# MCU063A_USB.net
KiCad netlist of a schematic drawn in Altium Designer
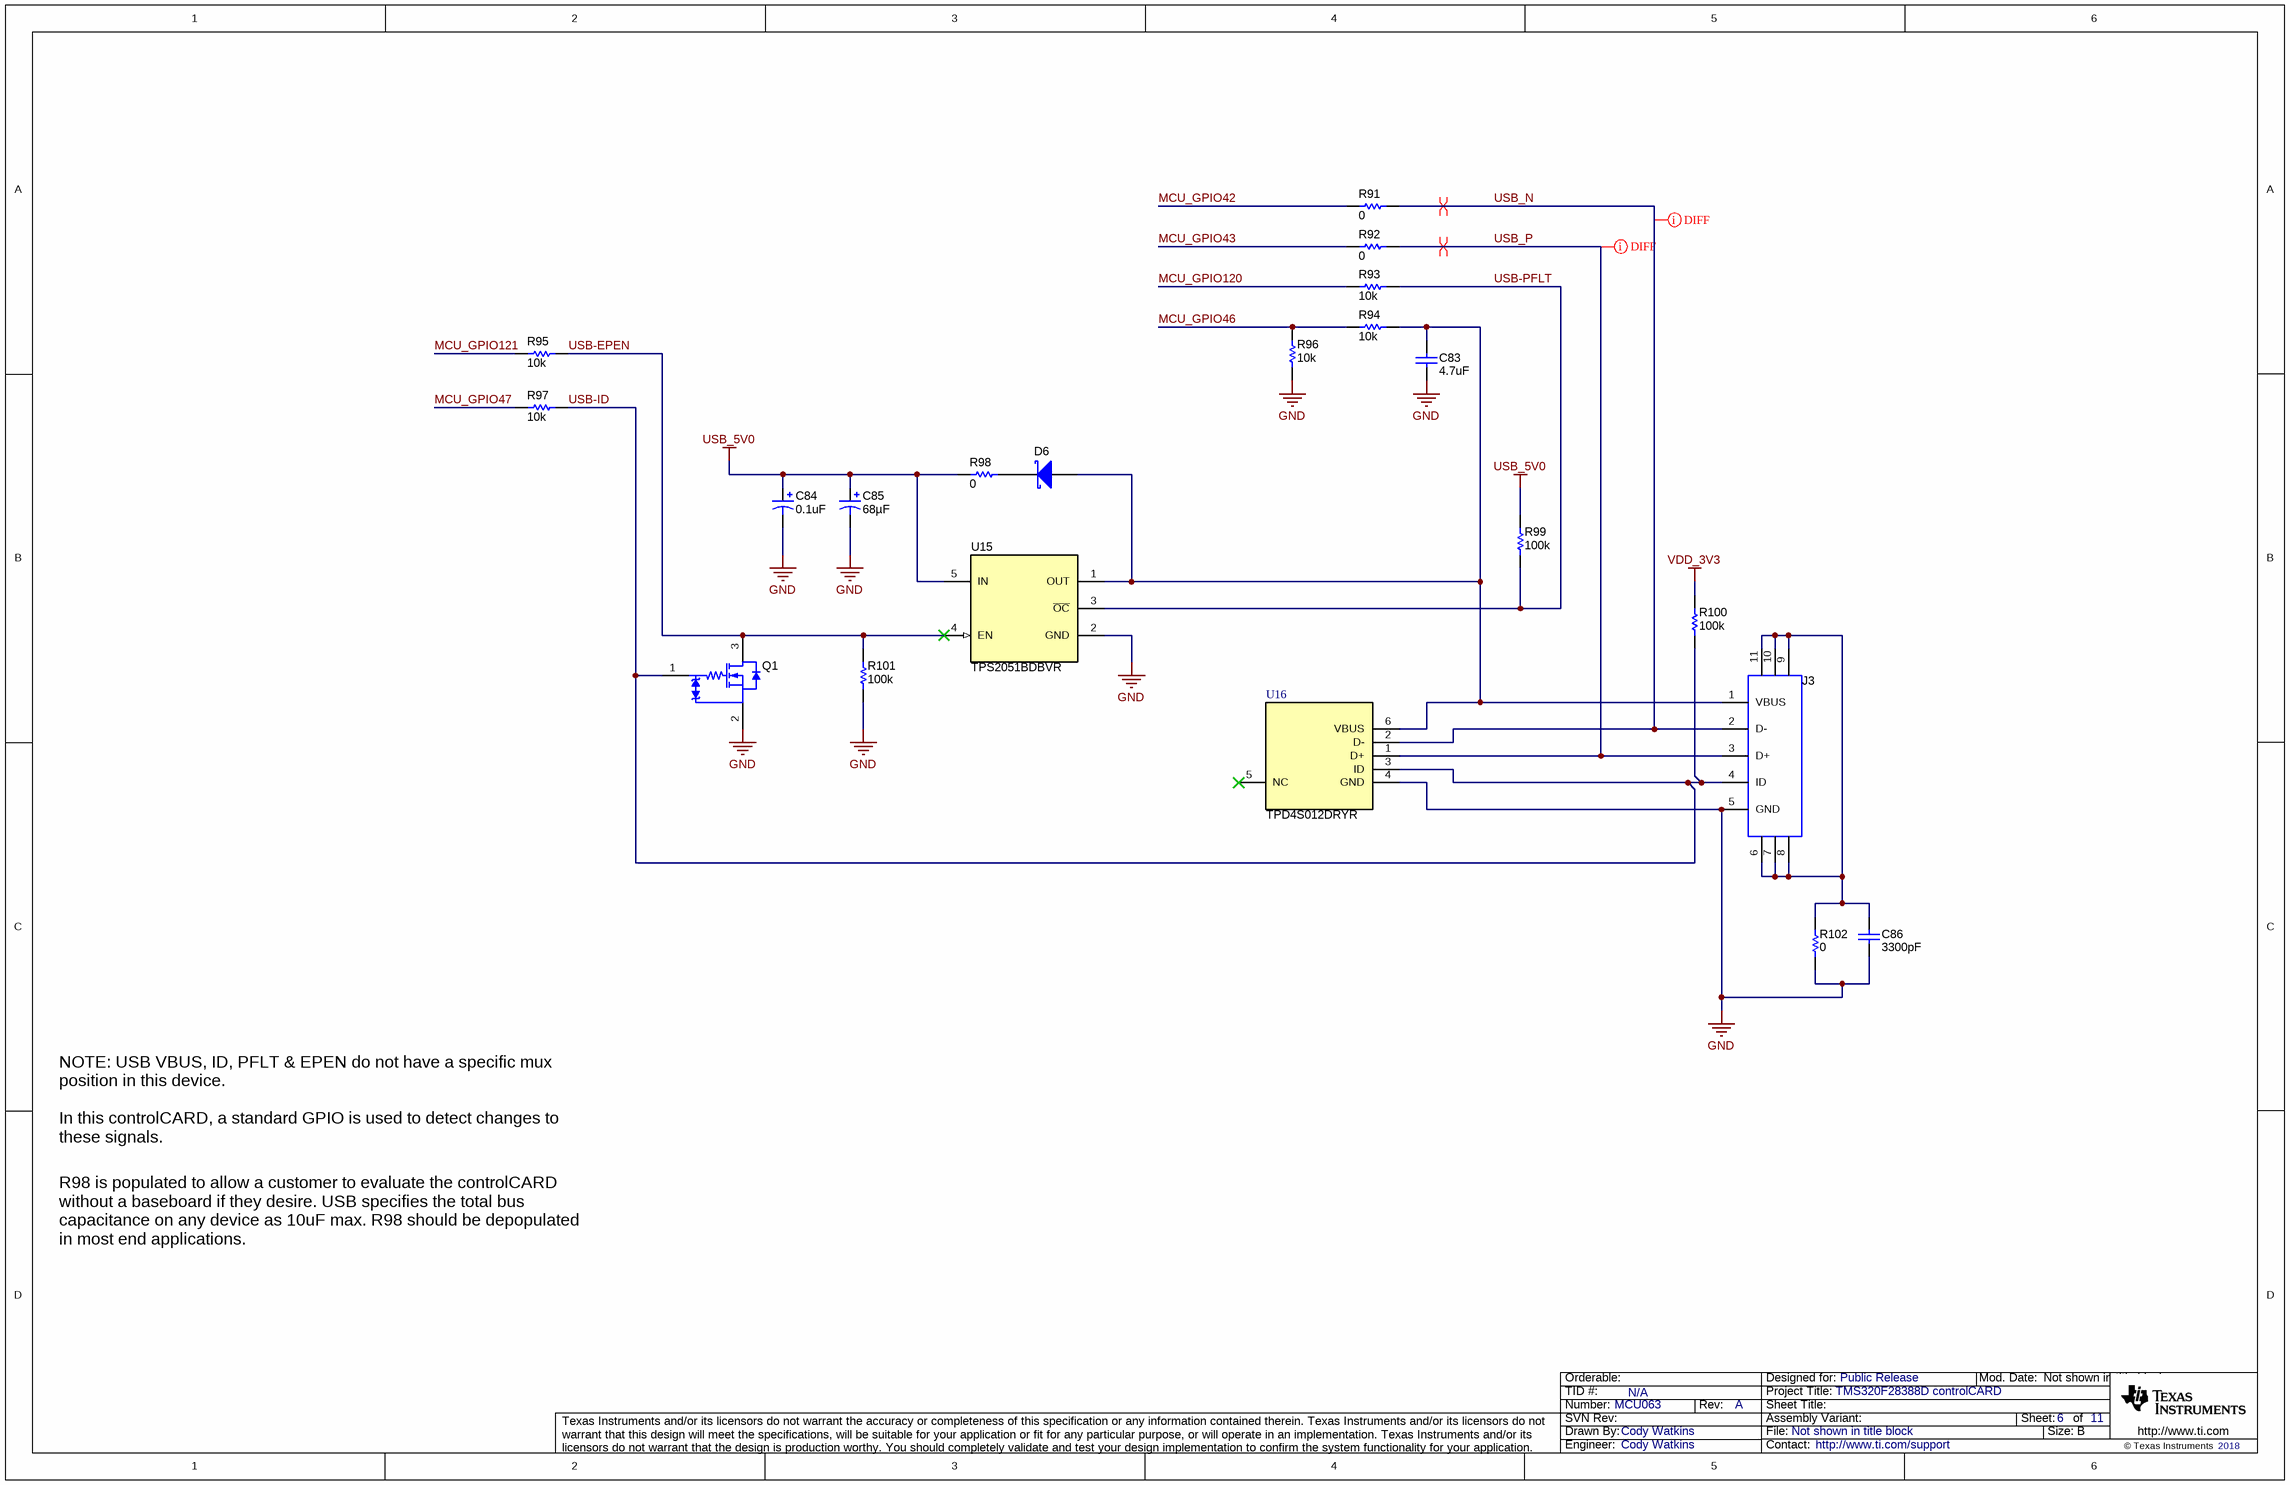
[diagram p0: MCU063A_USB.SchDoc]

(export (version "E")
  (design (tool "Eeschema 10.0.6"))
  (components
    (comp (ref "C83")
      (value "C0603C475K9PACTU")
      (footprint "0603")
      (description "CAP, CERM, 4.7 uF, 6.3 V, +/- 10%, X5R, 0603")
      (fields
        (field (name "MANUFACTURER") "Kemet")
        (field (name "VALUEDISPLAYED") "4.7uF")
        (field (name "PUBLISHER") "Texas Instruments")
      )
      (libsource (lib "Altium Vault - TI") (part "Capacitor"))
    )
    (comp (ref "C84")
      (value "293D104X9035A2TE3")
      (footprint "3216-18")
      (description "CAP, TA, 0.1 uF, 35 V, +/- 10%, 20 ohm, SMD")
      (fields
        (field (name "MANUFACTURER") "Vishay-Sprague")
        (field (name "VALUEDISPLAYED") "0.1uF")
        (field (name "PUBLISHER") "Texas Instruments")
      )
      (libsource (lib "Altium Vault - TI") (part "Cap_Polarized"))
    )
    (comp (ref "C85")
      (value "TLJA686M010R1500")
      (footprint "3216-18")
      (description "CAP, TA, 68 µF, 10 V, +/- 20%, 1.5 ohm, SMD")
      (fields (field (name "MANUFACTURER") "AVX") (field (name "VALUEDISPLAYED") "68µF"))
      (libsource (lib "Altium Vault - TI") (part "Cap_Polarized"))
    )
    (comp (ref "C86")
      (value "CGA2B2X7R1H332K050BA")
      (footprint "0402")
      (description "CAP, CERM, 3300 pF, 50 V, +/- 10%, X7R, AEC-Q200 Grade 1, 0402")
      (fields
        (field (name "MANUFACTURER") "TDK")
        (field (name "VALUEDISPLAYED") "3300pF")
        (field (name "PUBLISHER") "Texas Instruments")
      )
      (libsource (lib "Altium Vault - TI") (part "Capacitor"))
    )
    (comp (ref "D6")
      (value "MBRM110ET1G")
      (footprint "POWERMITE")
      (description "Diode, Schottky, 10 V, 1 A, AEC-Q101, POWERMITE")
      (fields (field (name "MANUFACTURER") "ON Semiconductor"))
      (libsource (lib "Altium Vault - TI") (part "DIODE_SCHOTTKY"))
    )
    (comp (ref "J3")
      (value "1051640001")
      (footprint "Molex_1051640001")
      (description "Receptacle, USB 2.0, Micro B, 5 Position, R/A, SMT")
      (fields (field (name "MANUFACTURER") "Molex") (field (name "PUBLISHER") "Texas Instruments"))
      (libsource (lib "Altium Vault - TI") (part "CONN_USB_MicroMini_6Shld"))
    )
    (comp (ref "Q1")
      (value "NTA7002NT1G")
      (footprint "SOT-416")
      (description "MOSFET, N-CH, 30 V, 0.154 A, AEC-Q101, SOT-416")
      (fields (field (name "MANUFACTURER") "ON Semiconductor"))
      (libsource (lib "Altium Vault - TI") (part "MOSFET_N_D3G1S2_PD5_RES"))
    )
    (comp (ref "R91")
      (value "CRCW04020000Z0ED")
      (footprint "0402")
      (description "RES, 0, 5%, 0.063 W, AEC-Q200 Grade 0, 0402")
      (fields (field (name "VALUEDISPLAYED") "0") (field (name "MANUFACTURER") "Vishay-Dale"))
      (libsource (lib "Altium Vault - TI") (part "Resistor"))
    )
    (comp (ref "R92")
      (value "CRCW04020000Z0ED")
      (footprint "0402")
      (description "RES, 0, 5%, 0.063 W, AEC-Q200 Grade 0, 0402")
      (fields (field (name "VALUEDISPLAYED") "0") (field (name "MANUFACTURER") "Vishay-Dale"))
      (libsource (lib "Altium Vault - TI") (part "Resistor"))
    )
    (comp (ref "R93")
      (value "ERJ-6GEYJ103V")
      (footprint "0805_HV")
      (description "RES, 10 k, 5%, 0.125 W, AEC-Q200 Grade 0, 0805")
      (fields (field (name "MANUFACTURER") "Panasonic") (field (name "VALUEDISPLAYED") "10k"))
      (libsource (lib "Altium Vault - TI") (part "Resistor"))
    )
    (comp (ref "R94")
      (value "ERJ-6GEYJ103V")
      (footprint "0805_HV")
      (description "RES, 10 k, 5%, 0.125 W, AEC-Q200 Grade 0, 0805")
      (fields (field (name "MANUFACTURER") "Panasonic") (field (name "VALUEDISPLAYED") "10k"))
      (libsource (lib "Altium Vault - TI") (part "Resistor"))
    )
    (comp (ref "R95")
      (value "ERJ-6GEYJ103V")
      (footprint "0805_HV")
      (description "RES, 10 k, 5%, 0.125 W, AEC-Q200 Grade 0, 0805")
      (fields (field (name "MANUFACTURER") "Panasonic") (field (name "VALUEDISPLAYED") "10k"))
      (libsource (lib "Altium Vault - TI") (part "Resistor"))
    )
    (comp (ref "R96")
      (value "ERJ-6GEYJ103V")
      (footprint "0805_HV")
      (description "RES, 10 k, 5%, 0.125 W, AEC-Q200 Grade 0, 0805")
      (fields (field (name "MANUFACTURER") "Panasonic") (field (name "VALUEDISPLAYED") "10k"))
      (libsource (lib "Altium Vault - TI") (part "Resistor"))
    )
    (comp (ref "R97")
      (value "ERJ-6GEYJ103V")
      (footprint "0805_HV")
      (description "RES, 10 k, 5%, 0.125 W, AEC-Q200 Grade 0, 0805")
      (fields (field (name "MANUFACTURER") "Panasonic") (field (name "VALUEDISPLAYED") "10k"))
      (libsource (lib "Altium Vault - TI") (part "Resistor"))
    )
    (comp (ref "R98")
      (value "CRCW04020000Z0ED")
      (footprint "0402")
      (description "RES, 0, 5%, 0.063 W, AEC-Q200 Grade 0, 0402")
      (fields (field (name "VALUEDISPLAYED") "0") (field (name "MANUFACTURER") "Vishay-Dale"))
      (libsource (lib "Altium Vault - TI") (part "Resistor"))
    )
    (comp (ref "R99")
      (value "ERJ-3GEYJ104V")
      (footprint "0603")
      (description "RES, 100 k, 5%, 0.1 W, AEC-Q200 Grade 0, 0603")
      (fields
        (field (name "MANUFACTURER") "Panasonic")
        (field (name "VALUEDISPLAYED") "100k")
        (field (name "PUBLISHER") "Texas Instruments")
      )
      (libsource (lib "Altium Vault - TI") (part "Resistor"))
    )
    (comp (ref "R100")
      (value "ERJ-3GEYJ104V")
      (footprint "0603")
      (description "RES, 100 k, 5%, 0.1 W, AEC-Q200 Grade 0, 0603")
      (fields
        (field (name "MANUFACTURER") "Panasonic")
        (field (name "VALUEDISPLAYED") "100k")
        (field (name "PUBLISHER") "Texas Instruments")
      )
      (libsource (lib "Altium Vault - TI") (part "Resistor"))
    )
    (comp (ref "R101")
      (value "ERJ-3GEYJ104V")
      (footprint "0603")
      (description "RES, 100 k, 5%, 0.1 W, AEC-Q200 Grade 0, 0603")
      (fields
        (field (name "MANUFACTURER") "Panasonic")
        (field (name "VALUEDISPLAYED") "100k")
        (field (name "PUBLISHER") "Texas Instruments")
      )
      (libsource (lib "Altium Vault - TI") (part "Resistor"))
    )
    (comp (ref "R102")
      (value "CRCW04020000Z0ED")
      (footprint "0402")
      (description "RES, 0, 5%, 0.063 W, AEC-Q200 Grade 0, 0402")
      (fields (field (name "VALUEDISPLAYED") "0") (field (name "MANUFACTURER") "Vishay-Dale"))
      (libsource (lib "Altium Vault - TI") (part "Resistor"))
    )
    (comp (ref "U15")
      (value "TPS2051BDBVR")
      (footprint "DBV0005A_N")
      (description "Single, Current-Limited, Power-Distribution Switch, DBV0005A (SOT-23-5)")
      (fields
        (field (name "ALTERNATE PARTNUMBER") "TPS2051BDBVT")
        (field (name "MANUFACTURER") "Texas Instruments")
        (field (name "PARTNUMBER") "TPS2051BDBVR")
        (field (name "PUBLISHER") "Texas Instruments")
      )
      (libsource (lib "Altium Vault - TI") (part "TPS2051DBV"))
    )
    (comp (ref "U16")
      (value "TPD4S012DRYR")
      (footprint "DRY0006A")
      (description "4-Channel USB ESD Solution with Power Clamp, DRY0006A (USON-6)")
      (fields (field (name "MANUFACTURER") "Texas Instruments") (field (name "PARTNUMBER") "TPD4S012DRYR"))
      (libsource (lib "Altium Vault - TI") (part "TI-TPD4S012-SON_DRY-6"))
    )
  )
  (nets
    (net (code "1") (name "/MCU_GPIO42") (class "Default")
      (node (ref "R91") (pin "1") (pinfunction "1_1") (pintype "passive"))
    )
    (net (code "2") (name "/MCU_GPIO43") (class "Default")
      (node (ref "R92") (pin "1") (pinfunction "1_1") (pintype "passive"))
    )
    (net (code "3") (name "/MCU_GPIO46") (class "Default")
      (node (ref "R94") (pin "1") (pinfunction "1_1") (pintype "passive"))
      (node (ref "R96") (pin "2") (pinfunction "2_2") (pintype "passive"))
    )
    (net (code "4") (name "/MCU_GPIO47") (class "Default")
      (node (ref "R97") (pin "1") (pinfunction "1_1") (pintype "passive"))
    )
    (net (code "5") (name "/MCU_GPIO120") (class "Default")
      (node (ref "R93") (pin "1") (pinfunction "1_1") (pintype "passive"))
    )
    (net (code "6") (name "/MCU_GPIO121") (class "Default")
      (node (ref "R95") (pin "1") (pinfunction "1_1") (pintype "passive"))
    )
    (net (code "7") (name "/USB-EPEN") (class "Default")
      (node (ref "Q1") (pin "3") (pinfunction "D_3") (pintype "passive"))
      (node (ref "R101") (pin "1") (pinfunction "1_1") (pintype "passive"))
      (node (ref "R95") (pin "2") (pinfunction "2_2") (pintype "passive"))
      (node (ref "U15") (pin "4") (pinfunction "EN_4") (pintype "input"))
    )
    (net (code "8") (name "/USB-ID") (class "Default")
      (node (ref "J3") (pin "4") (pinfunction "ID_4") (pintype "passive"))
      (node (ref "Q1") (pin "1") (pinfunction "G_1") (pintype "passive"))
      (node (ref "R100") (pin "2") (pinfunction "2_2") (pintype "passive"))
      (node (ref "R97") (pin "2") (pinfunction "2_2") (pintype "passive"))
      (node (ref "U16") (pin "3") (pinfunction "ID_3") (pintype "passive"))
    )
    (net (code "9") (name "/USB-PFLT") (class "Default")
      (node (ref "R93") (pin "2") (pinfunction "2_2") (pintype "passive"))
      (node (ref "R99") (pin "2") (pinfunction "2_2") (pintype "passive"))
      (node (ref "U15") (pin "3") (pinfunction "OC_3") (pintype "open_collector"))
    )
    (net (code "10") (name "/USB_N") (class "Default")
      (node (ref "J3") (pin "2") (pinfunction "D-_2") (pintype "passive"))
      (node (ref "R91") (pin "2") (pinfunction "2_2") (pintype "passive"))
      (node (ref "U16") (pin "2") (pinfunction "D-_2") (pintype "passive"))
    )
    (net (code "11") (name "/USB_P") (class "Default")
      (node (ref "J3") (pin "3") (pinfunction "D+_3") (pintype "passive"))
      (node (ref "R92") (pin "2") (pinfunction "2_2") (pintype "passive"))
      (node (ref "U16") (pin "1") (pinfunction "D+_1") (pintype "passive"))
    )
    (net (code "12") (name "GND") (class "Default")
      (node (ref "C83") (pin "2") (pinfunction "2_2") (pintype "passive"))
      (node (ref "C84") (pin "2") (pinfunction "-_2") (pintype "passive"))
      (node (ref "C85") (pin "2") (pinfunction "-_2") (pintype "passive"))
      (node (ref "C86") (pin "1") (pinfunction "1_1") (pintype "passive"))
      (node (ref "J3") (pin "5") (pinfunction "GND_5") (pintype "passive"))
      (node (ref "Q1") (pin "2") (pinfunction "S_2") (pintype "passive"))
      (node (ref "R101") (pin "2") (pinfunction "2_2") (pintype "passive"))
      (node (ref "R102") (pin "2") (pinfunction "2_2") (pintype "passive"))
      (node (ref "R96") (pin "1") (pinfunction "1_1") (pintype "passive"))
      (node (ref "U15") (pin "2") (pinfunction "GND_2") (pintype "power_in"))
      (node (ref "U16") (pin "4") (pinfunction "GND_4") (pintype "power_in"))
    )
    (net (code "13") (name "Net-(C86-Pad2)") (class "Default")
      (node (ref "C86") (pin "2") (pinfunction "2_2") (pintype "passive"))
      (node (ref "J3") (pin "10") (pinfunction "10_10") (pintype "passive"))
      (node (ref "J3") (pin "11") (pinfunction "11_11") (pintype "passive"))
      (node (ref "J3") (pin "6") (pinfunction "6_6") (pintype "passive"))
      (node (ref "J3") (pin "7") (pinfunction "7_7") (pintype "passive"))
      (node (ref "J3") (pin "8") (pinfunction "8_8") (pintype "passive"))
      (node (ref "J3") (pin "9") (pinfunction "9_9") (pintype "passive"))
      (node (ref "R102") (pin "1") (pinfunction "1_1") (pintype "passive"))
    )
    (net (code "14") (name "Net-(D6-A)") (class "Default")
      (node (ref "C83") (pin "1") (pinfunction "1_1") (pintype "passive"))
      (node (ref "D6") (pin "2") (pinfunction "A_2") (pintype "passive"))
      (node (ref "J3") (pin "1") (pinfunction "VBUS_1") (pintype "passive"))
      (node (ref "R94") (pin "2") (pinfunction "2_2") (pintype "passive"))
      (node (ref "U15") (pin "1") (pinfunction "OUT_1") (pintype "power_in"))
      (node (ref "U16") (pin "6") (pinfunction "VBUS_6") (pintype "passive"))
    )
    (net (code "15") (name "Net-(D6-K)") (class "Default")
      (node (ref "D6") (pin "1") (pinfunction "K_1") (pintype "passive"))
      (node (ref "R98") (pin "2") (pinfunction "2_2") (pintype "passive"))
    )
    (net (code "16") (name "USB_5V0") (class "Default")
      (node (ref "C84") (pin "1") (pinfunction "+_1") (pintype "passive"))
      (node (ref "C85") (pin "1") (pinfunction "+_1") (pintype "passive"))
      (node (ref "R98") (pin "1") (pinfunction "1_1") (pintype "passive"))
      (node (ref "R99") (pin "1") (pinfunction "1_1") (pintype "passive"))
      (node (ref "U15") (pin "5") (pinfunction "IN_5") (pintype "power_in"))
    )
    (net (code "17") (name "VDD_3V3") (class "Default")
      (node (ref "R100") (pin "1") (pinfunction "1_1") (pintype "passive"))
    )
    (net (code "18") (name "unconnected-(U16-NC-Pad5)") (class "Default")
      (node (ref "U16") (pin "5") (pinfunction "NC_5") (pintype "passive+no_connect"))
    )
  )
)
